# ControleLeds.net
KiCad netlist of a schematic drawn in Altium Designer
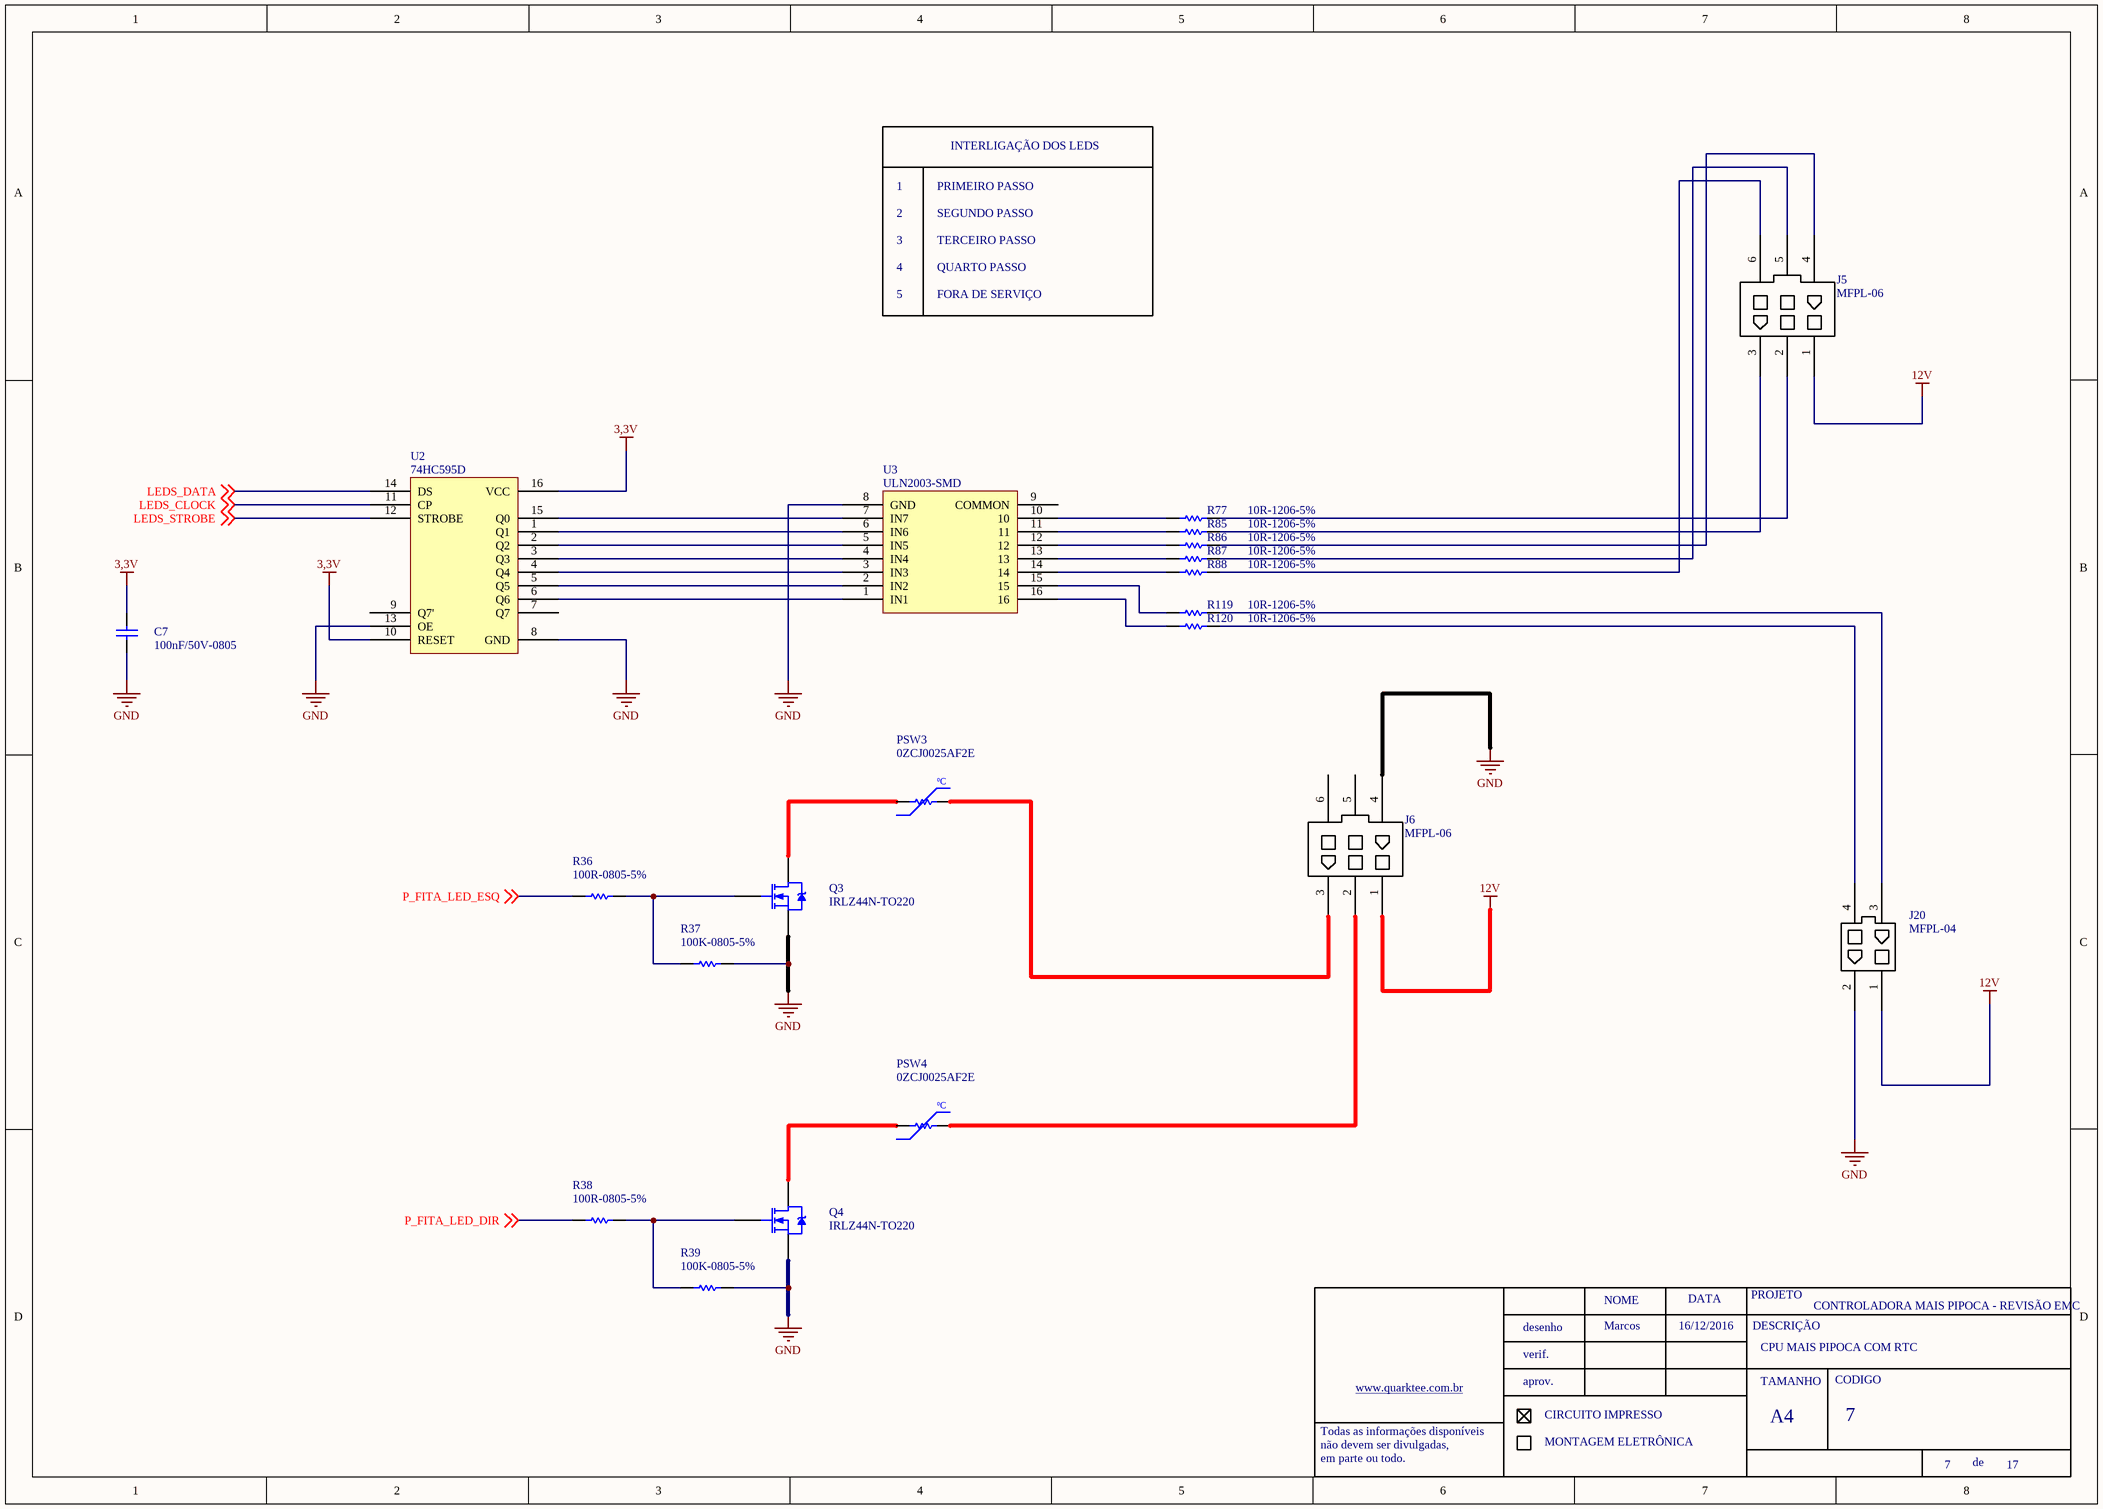
[diagram p0: ControleLeds.SchDoc]

(export (version "E")
  (design (tool "Eeschema 10.0.6"))
  (components
    (comp (ref "C7")
      (value "100nF/50V-0805")
      (footprint "0805-REVISADO ONDA")
      (description "100nF/50-0805-NPO")
      (libsource (lib "AquinoLib") (part "100nF/50-0805-NPO"))
    )
    (comp (ref "J5") (value "MFPL-06") (libsource (lib "AquinoLib") (part "MFPL-06")))
    (comp (ref "J6") (value "MFPL-06") (libsource (lib "AquinoLib") (part "MFPL-06")))
    (comp (ref "J20") (value "MFPL-04") (libsource (lib "AquinoLib") (part "MFPL-04")))
    (comp (ref "PSW3")
      (value "0ZCJ0025AF2E")
      (footprint "1206-REVISADO ONDA")
      (description "PTC 2A-120V")
      (libsource (lib "AquinoLib") (part "PTC 2A-120V"))
    )
    (comp (ref "PSW4")
      (value "0ZCJ0025AF2E")
      (footprint "1206-REVISADO ONDA")
      (description "PTC 2A-120V")
      (libsource (lib "AquinoLib") (part "PTC 2A-120V"))
    )
    (comp (ref "Q3")
      (value "IRLZ44N-TO220")
      (footprint "TO220-3 EM PÉ")
      (libsource (lib "ChaveDigital3") (part "IRLZ44N-TO220"))
    )
    (comp (ref "Q4")
      (value "IRLZ44N-TO220")
      (footprint "TO220-3 EM PÉ")
      (libsource (lib "ChaveDigital3") (part "IRLZ44N-TO220"))
    )
    (comp (ref "R36")
      (value "100R-0805-5%")
      (footprint "0805-REVISADO ONDA")
      (libsource (lib "AquinoLib") (part "100R-0805-5%"))
    )
    (comp (ref "R37")
      (value "100K-0805-5%")
      (footprint "0805-REVISADO ONDA")
      (libsource (lib "AquinoLib") (part "100K-0805-5%"))
    )
    (comp (ref "R38")
      (value "100R-0805-5%")
      (footprint "0805-REVISADO ONDA")
      (libsource (lib "AquinoLib") (part "100R-0805-5%"))
    )
    (comp (ref "R39")
      (value "100K-0805-5%")
      (footprint "0805-REVISADO ONDA")
      (libsource (lib "AquinoLib") (part "100K-0805-5%"))
    )
    (comp (ref "R77")
      (value "10R-1206-5%")
      (footprint "1206-REVISADO ONDA")
      (description "10R-0805-5%")
      (libsource (lib "AquinoLib") (part "10R-0805-5%"))
    )
    (comp (ref "R85")
      (value "10R-1206-5%")
      (footprint "1206-REVISADO ONDA")
      (description "10R-0805-5%")
      (libsource (lib "AquinoLib") (part "10R-0805-5%"))
    )
    (comp (ref "R86")
      (value "10R-1206-5%")
      (footprint "1206-REVISADO ONDA")
      (description "10R-0805-5%")
      (libsource (lib "AquinoLib") (part "10R-0805-5%"))
    )
    (comp (ref "R87")
      (value "10R-1206-5%")
      (footprint "1206-REVISADO ONDA")
      (description "10R-0805-5%")
      (libsource (lib "AquinoLib") (part "10R-0805-5%"))
    )
    (comp (ref "R88")
      (value "10R-1206-5%")
      (footprint "1206-REVISADO ONDA")
      (description "10R-0805-5%")
      (libsource (lib "AquinoLib") (part "10R-0805-5%"))
    )
    (comp (ref "R119")
      (value "10R-1206-5%")
      (footprint "1206-REVISADO ONDA")
      (description "10R-0805-5%")
      (libsource (lib "AquinoLib") (part "10R-0805-5%"))
    )
    (comp (ref "R120")
      (value "10R-1206-5%")
      (footprint "1206-REVISADO ONDA")
      (description "10R-0805-5%")
      (libsource (lib "AquinoLib") (part "10R-0805-5%"))
    )
    (comp (ref "U2")
      (value "74HC595D")
      (footprint "SOIC 16 PINOS")
      (libsource (lib "ChaveDigital3") (part "74HC595D"))
    )
    (comp (ref "U3")
      (value "ULN2003-SMD")
      (footprint "SOIC 16 PINOS")
      (description "ULN2003")
      (libsource (lib "AquinoLib") (part "ULN2003"))
    )
  )
  (nets
    (net (code "1") (name "3,3V") (class "Default")
      (node (ref "C7") (pin "2") (pinfunction "2_2") (pintype "passive"))
      (node (ref "U2") (pin "10") (pinfunction "RESET_10") (pintype "passive"))
      (node (ref "U2") (pin "16") (pinfunction "VCC_16") (pintype "passive"))
    )
    (net (code "2") (name "12V") (class "Default")
      (node (ref "J20") (pin "1") (pinfunction "1_1") (pintype "passive"))
      (node (ref "J5") (pin "1") (pinfunction "1_1") (pintype "passive"))
      (node (ref "J6") (pin "1") (pinfunction "1_1") (pintype "passive"))
    )
    (net (code "3") (name "GND") (class "Default")
      (node (ref "C7") (pin "1") (pinfunction "1_1") (pintype "passive"))
      (node (ref "J20") (pin "2") (pinfunction "2_2") (pintype "passive"))
      (node (ref "J6") (pin "4") (pinfunction "4_4") (pintype "passive"))
      (node (ref "Q3") (pin "3") (pinfunction "S_3") (pintype "passive"))
      (node (ref "Q4") (pin "3") (pinfunction "S_3") (pintype "passive"))
      (node (ref "R37") (pin "2") (pinfunction "2_2") (pintype "passive"))
      (node (ref "R39") (pin "2") (pinfunction "2_2") (pintype "passive"))
      (node (ref "U2") (pin "13") (pinfunction "OE_13") (pintype "passive"))
      (node (ref "U2") (pin "8") (pinfunction "GND_8") (pintype "passive"))
      (node (ref "U3") (pin "8") (pinfunction "GND_8") (pintype "passive"))
    )
    (net (code "4") (name "LEDS_CLOCK") (class "Default")
      (node (ref "U2") (pin "11") (pinfunction "CP_11") (pintype "passive"))
    )
    (net (code "5") (name "LEDS_DATA") (class "Default")
      (node (ref "U2") (pin "14") (pinfunction "DS_14") (pintype "passive"))
    )
    (net (code "6") (name "LEDS_STROBE") (class "Default")
      (node (ref "U2") (pin "12") (pinfunction "STROBE_12") (pintype "passive"))
    )
    (net (code "7") (name "Net-(J5-Pad2)") (class "Default")
      (node (ref "J5") (pin "2") (pinfunction "2_2") (pintype "passive"))
      (node (ref "R77") (pin "2") (pinfunction "2_2") (pintype "passive"))
    )
    (net (code "8") (name "Net-(J5-Pad3)") (class "Default")
      (node (ref "J5") (pin "3") (pinfunction "3_3") (pintype "passive"))
      (node (ref "R85") (pin "2") (pinfunction "2_2") (pintype "passive"))
    )
    (net (code "9") (name "Net-(J5-Pad4)") (class "Default")
      (node (ref "J5") (pin "4") (pinfunction "4_4") (pintype "passive"))
      (node (ref "R86") (pin "2") (pinfunction "2_2") (pintype "passive"))
    )
    (net (code "10") (name "Net-(J5-Pad5)") (class "Default")
      (node (ref "J5") (pin "5") (pinfunction "5_5") (pintype "passive"))
      (node (ref "R87") (pin "2") (pinfunction "2_2") (pintype "passive"))
    )
    (net (code "11") (name "Net-(J5-Pad6)") (class "Default")
      (node (ref "J5") (pin "6") (pinfunction "6_6") (pintype "passive"))
      (node (ref "R88") (pin "2") (pinfunction "2_2") (pintype "passive"))
    )
    (net (code "12") (name "Net-(J6-Pad2)") (class "Default")
      (node (ref "J6") (pin "2") (pinfunction "2_2") (pintype "passive"))
      (node (ref "PSW4") (pin "2") (pinfunction "2_2") (pintype "passive"))
    )
    (net (code "13") (name "Net-(J6-Pad3)") (class "Default")
      (node (ref "J6") (pin "3") (pinfunction "3_3") (pintype "passive"))
      (node (ref "PSW3") (pin "2") (pinfunction "2_2") (pintype "passive"))
    )
    (net (code "14") (name "Net-(J20-Pad3)") (class "Default")
      (node (ref "J20") (pin "3") (pinfunction "3_3") (pintype "passive"))
      (node (ref "R119") (pin "2") (pinfunction "2_2") (pintype "passive"))
    )
    (net (code "15") (name "Net-(J20-Pad4)") (class "Default")
      (node (ref "J20") (pin "4") (pinfunction "4_4") (pintype "passive"))
      (node (ref "R120") (pin "2") (pinfunction "2_2") (pintype "passive"))
    )
    (net (code "16") (name "Net-(Q3-D)") (class "Default")
      (node (ref "PSW3") (pin "1") (pinfunction "1_1") (pintype "passive"))
      (node (ref "Q3") (pin "2") (pinfunction "D_2") (pintype "passive"))
    )
    (net (code "17") (name "Net-(Q3-G)") (class "Default")
      (node (ref "Q3") (pin "1") (pinfunction "G_1") (pintype "passive"))
      (node (ref "R36") (pin "2") (pinfunction "2_2") (pintype "passive"))
      (node (ref "R37") (pin "1") (pinfunction "1_1") (pintype "passive"))
    )
    (net (code "18") (name "Net-(Q4-D)") (class "Default")
      (node (ref "PSW4") (pin "1") (pinfunction "1_1") (pintype "passive"))
      (node (ref "Q4") (pin "2") (pinfunction "D_2") (pintype "passive"))
    )
    (net (code "19") (name "Net-(Q4-G)") (class "Default")
      (node (ref "Q4") (pin "1") (pinfunction "G_1") (pintype "passive"))
      (node (ref "R38") (pin "2") (pinfunction "2_2") (pintype "passive"))
      (node (ref "R39") (pin "1") (pinfunction "1_1") (pintype "passive"))
    )
    (net (code "20") (name "Net-(R77-Pad1)") (class "Default")
      (node (ref "R77") (pin "1") (pinfunction "1_1") (pintype "passive"))
      (node (ref "U3") (pin "10") (pinfunction "10_10") (pintype "passive"))
    )
    (net (code "21") (name "Net-(R85-Pad1)") (class "Default")
      (node (ref "R85") (pin "1") (pinfunction "1_1") (pintype "passive"))
      (node (ref "U3") (pin "11") (pinfunction "11_11") (pintype "passive"))
    )
    (net (code "22") (name "Net-(R86-Pad1)") (class "Default")
      (node (ref "R86") (pin "1") (pinfunction "1_1") (pintype "passive"))
      (node (ref "U3") (pin "12") (pinfunction "12_12") (pintype "passive"))
    )
    (net (code "23") (name "Net-(R87-Pad1)") (class "Default")
      (node (ref "R87") (pin "1") (pinfunction "1_1") (pintype "passive"))
      (node (ref "U3") (pin "13") (pinfunction "13_13") (pintype "passive"))
    )
    (net (code "24") (name "Net-(R88-Pad1)") (class "Default")
      (node (ref "R88") (pin "1") (pinfunction "1_1") (pintype "passive"))
      (node (ref "U3") (pin "14") (pinfunction "14_14") (pintype "passive"))
    )
    (net (code "25") (name "Net-(R119-Pad1)") (class "Default")
      (node (ref "R119") (pin "1") (pinfunction "1_1") (pintype "passive"))
      (node (ref "U3") (pin "15") (pinfunction "15_15") (pintype "passive"))
    )
    (net (code "26") (name "Net-(R120-Pad1)") (class "Default")
      (node (ref "R120") (pin "1") (pinfunction "1_1") (pintype "passive"))
      (node (ref "U3") (pin "16") (pinfunction "16_16") (pintype "passive"))
    )
    (net (code "27") (name "Net-(U2-Q0)") (class "Default")
      (node (ref "U2") (pin "15") (pinfunction "Q0_15") (pintype "passive"))
      (node (ref "U3") (pin "7") (pinfunction "IN7_7") (pintype "passive"))
    )
    (net (code "28") (name "Net-(U2-Q1)") (class "Default")
      (node (ref "U2") (pin "1") (pinfunction "Q1_1") (pintype "passive"))
      (node (ref "U3") (pin "6") (pinfunction "IN6_6") (pintype "passive"))
    )
    (net (code "29") (name "Net-(U2-Q2)") (class "Default")
      (node (ref "U2") (pin "2") (pinfunction "Q2_2") (pintype "passive"))
      (node (ref "U3") (pin "5") (pinfunction "IN5_5") (pintype "passive"))
    )
    (net (code "30") (name "Net-(U2-Q3)") (class "Default")
      (node (ref "U2") (pin "3") (pinfunction "Q3_3") (pintype "passive"))
      (node (ref "U3") (pin "4") (pinfunction "IN4_4") (pintype "passive"))
    )
    (net (code "31") (name "Net-(U2-Q4)") (class "Default")
      (node (ref "U2") (pin "4") (pinfunction "Q4_4") (pintype "passive"))
      (node (ref "U3") (pin "3") (pinfunction "IN3_3") (pintype "passive"))
    )
    (net (code "32") (name "Net-(U2-Q5)") (class "Default")
      (node (ref "U2") (pin "5") (pinfunction "Q5_5") (pintype "passive"))
      (node (ref "U3") (pin "2") (pinfunction "IN2_2") (pintype "passive"))
    )
    (net (code "33") (name "Net-(U2-Q6)") (class "Default")
      (node (ref "U2") (pin "6") (pinfunction "Q6_6") (pintype "passive"))
      (node (ref "U3") (pin "1") (pinfunction "IN1_1") (pintype "passive"))
    )
    (net (code "34") (name "P_FITA_LED_DIR") (class "Default")
      (node (ref "R38") (pin "1") (pinfunction "1_1") (pintype "passive"))
    )
    (net (code "35") (name "P_FITA_LED_ESQ") (class "Default")
      (node (ref "R36") (pin "1") (pinfunction "1_1") (pintype "passive"))
    )
    (net (code "36") (name "unconnected-(J6-Pad5)") (class "Default")
      (node (ref "J6") (pin "5") (pinfunction "5_5") (pintype "passive"))
    )
    (net (code "37") (name "unconnected-(J6-Pad6)") (class "Default")
      (node (ref "J6") (pin "6") (pinfunction "6_6") (pintype "passive"))
    )
    (net (code "38") (name "unconnected-(U2-Q7'-Pad9)") (class "Default")
      (node (ref "U2") (pin "9") (pinfunction "Q7'_9") (pintype "passive"))
    )
    (net (code "39") (name "unconnected-(U2-Q7-Pad7)") (class "Default")
      (node (ref "U2") (pin "7") (pinfunction "Q7_7") (pintype "passive"))
    )
    (net (code "40") (name "unconnected-(U3-COMMON-Pad9)") (class "Default")
      (node (ref "U3") (pin "9") (pinfunction "COMMON_9") (pintype "passive"))
    )
  )
)
